# controller_main_board.net
KiCad netlist of a schematic drawn in EAGLE
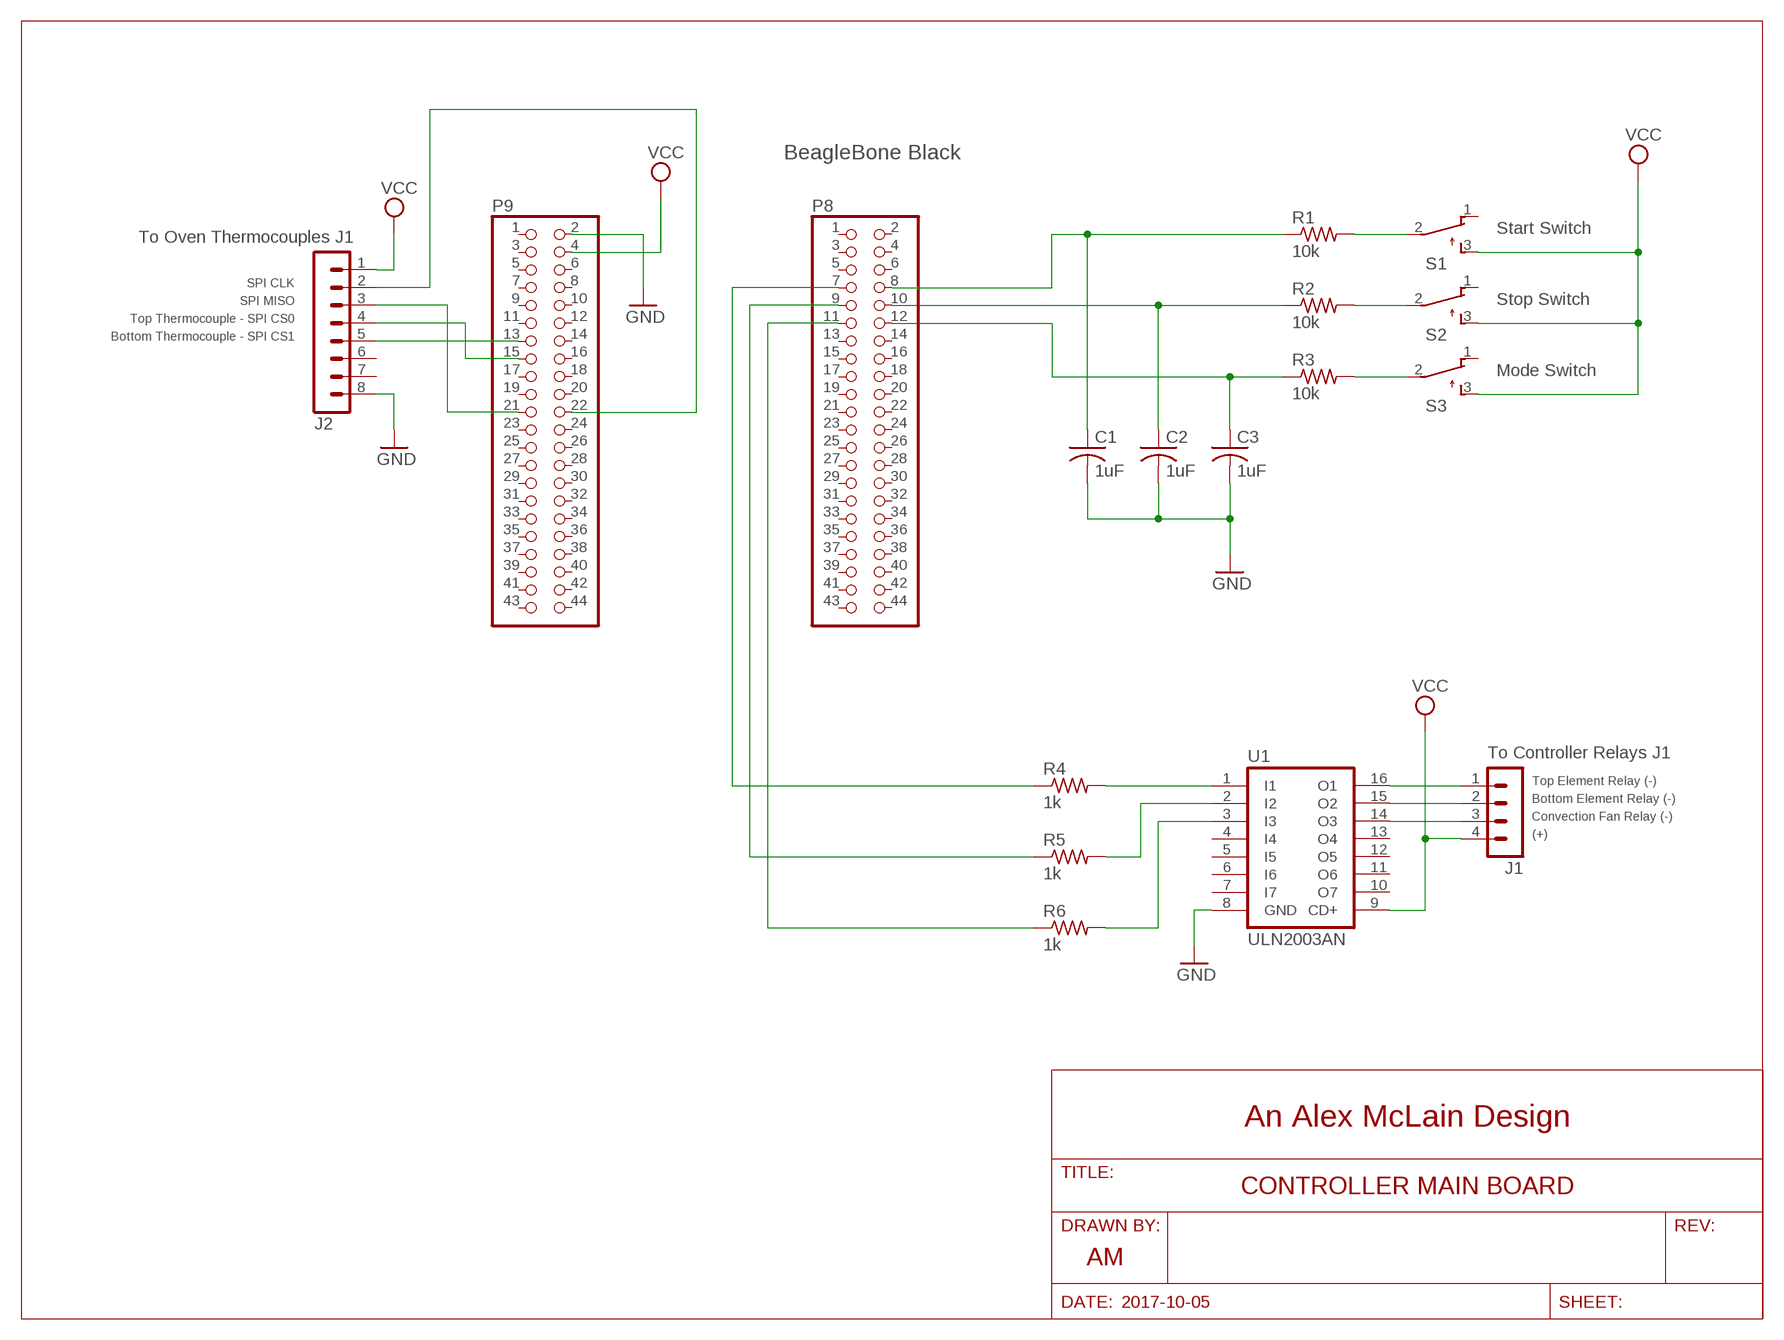
[diagram p0: schematic, sheet 1]

(export (version "E")
  (design (tool "Eeschema 10.0.6"))
  (components
    (comp (ref "C1")
      (value "1uF")
      (footprint "eagle-import:C025-050X050")
      (libsource (lib "eagle-import") (part "C-US025-050X050"))
    )
    (comp (ref "C2")
      (value "1uF")
      (footprint "eagle-import:C025-050X050")
      (libsource (lib "eagle-import") (part "C-US025-050X050"))
    )
    (comp (ref "C3")
      (value "1uF")
      (footprint "eagle-import:C025-050X050")
      (libsource (lib "eagle-import") (part "C-US025-050X050"))
    )
    (comp (ref "J1")
      (value "MA04-1")
      (footprint "eagle-import:MA04-1")
      (libsource (lib "eagle-import") (part "MA04-1"))
    )
    (comp (ref "J2")
      (value "MA08-1")
      (footprint "eagle-import:MA08-1")
      (libsource (lib "eagle-import") (part "MA08-1"))
    )
    (comp (ref "P8")
      (value "PINHD-2X22")
      (footprint "eagle-import:2X22")
      (libsource (lib "eagle-import") (part "PINHD-2X22"))
    )
    (comp (ref "P9")
      (value "PINHD-2X22")
      (footprint "eagle-import:2X22")
      (libsource (lib "eagle-import") (part "PINHD-2X22"))
    )
    (comp (ref "R1")
      (value "10k")
      (footprint "eagle-import:0204_7")
      (libsource (lib "eagle-import") (part "R-US_0204/7"))
    )
    (comp (ref "R2")
      (value "10k")
      (footprint "eagle-import:0204_7")
      (libsource (lib "eagle-import") (part "R-US_0204/7"))
    )
    (comp (ref "R3")
      (value "10k")
      (footprint "eagle-import:0204_7")
      (libsource (lib "eagle-import") (part "R-US_0204/7"))
    )
    (comp (ref "R4")
      (value "1k")
      (footprint "eagle-import:0204_7")
      (libsource (lib "eagle-import") (part "R-US_0204/7"))
    )
    (comp (ref "R5")
      (value "1k")
      (footprint "eagle-import:0204_7")
      (libsource (lib "eagle-import") (part "R-US_0204/7"))
    )
    (comp (ref "R6")
      (value "1k")
      (footprint "eagle-import:0204_7")
      (libsource (lib "eagle-import") (part "R-US_0204/7"))
    )
    (comp (ref "S1")
      (value "TL32PO")
      (footprint "eagle-import:TL3XPO")
      (libsource (lib "eagle-import") (part "TL32PO"))
    )
    (comp (ref "S2")
      (value "TL32PO")
      (footprint "eagle-import:TL3XPO")
      (libsource (lib "eagle-import") (part "TL32PO"))
    )
    (comp (ref "S3")
      (value "TL32PO")
      (footprint "eagle-import:TL3XPO")
      (libsource (lib "eagle-import") (part "TL32PO"))
    )
    (comp (ref "U1")
      (value "ULN2003AN")
      (footprint "eagle-import:DIL16")
      (libsource (lib "eagle-import") (part "ULN2003AN"))
    )
  )
  (nets
    (net (code "1") (name "GND") (class "Default")
      (node (ref "C1") (pin "2") (pinfunction "2_2") (pintype "passive"))
      (node (ref "C2") (pin "2") (pinfunction "2_2") (pintype "passive"))
      (node (ref "C3") (pin "2") (pinfunction "2_2") (pintype "passive"))
      (node (ref "J2") (pin "8") (pinfunction "8_8") (pintype "passive"))
      (node (ref "P9") (pin "2") (pinfunction "2_2") (pintype "passive"))
      (node (ref "U1") (pin "8") (pinfunction "GND_8") (pintype "power_in"))
    )
    (net (code "2") (name "Net-(C1-Pad1)") (class "Default")
      (node (ref "C1") (pin "1") (pinfunction "1_1") (pintype "passive"))
      (node (ref "P8") (pin "8") (pinfunction "8_8") (pintype "passive"))
      (node (ref "R1") (pin "1") (pinfunction "1_1") (pintype "passive"))
    )
    (net (code "3") (name "Net-(C2-Pad1)") (class "Default")
      (node (ref "C2") (pin "1") (pinfunction "1_1") (pintype "passive"))
      (node (ref "P8") (pin "10") (pinfunction "10_10") (pintype "passive"))
      (node (ref "R2") (pin "1") (pinfunction "1_1") (pintype "passive"))
    )
    (net (code "4") (name "Net-(C3-Pad1)") (class "Default")
      (node (ref "C3") (pin "1") (pinfunction "1_1") (pintype "passive"))
      (node (ref "P8") (pin "12") (pinfunction "12_12") (pintype "passive"))
      (node (ref "R3") (pin "1") (pinfunction "1_1") (pintype "passive"))
    )
    (net (code "5") (name "Net-(J2-Pad2)") (class "Default")
      (node (ref "J2") (pin "2") (pinfunction "2_2") (pintype "passive"))
      (node (ref "P9") (pin "22") (pinfunction "22_22") (pintype "passive"))
    )
    (net (code "6") (name "Net-(J2-Pad3)") (class "Default")
      (node (ref "J2") (pin "3") (pinfunction "3_3") (pintype "passive"))
      (node (ref "P9") (pin "21") (pinfunction "21_21") (pintype "passive"))
    )
    (net (code "7") (name "Net-(J2-Pad4)") (class "Default")
      (node (ref "J2") (pin "4") (pinfunction "4_4") (pintype "passive"))
      (node (ref "P9") (pin "15") (pinfunction "15_15") (pintype "passive"))
    )
    (net (code "8") (name "Net-(J2-Pad5)") (class "Default")
      (node (ref "J2") (pin "5") (pinfunction "5_5") (pintype "passive"))
      (node (ref "P9") (pin "13") (pinfunction "13_13") (pintype "passive"))
    )
    (net (code "9") (name "Net-(P8-Pad7)") (class "Default")
      (node (ref "P8") (pin "7") (pinfunction "7_7") (pintype "passive"))
      (node (ref "R4") (pin "1") (pinfunction "1_1") (pintype "passive"))
    )
    (net (code "10") (name "Net-(P8-Pad9)") (class "Default")
      (node (ref "P8") (pin "9") (pinfunction "9_9") (pintype "passive"))
      (node (ref "R5") (pin "1") (pinfunction "1_1") (pintype "passive"))
    )
    (net (code "11") (name "Net-(P8-Pad11)") (class "Default")
      (node (ref "P8") (pin "11") (pinfunction "11_11") (pintype "passive"))
      (node (ref "R6") (pin "1") (pinfunction "1_1") (pintype "passive"))
    )
    (net (code "12") (name "Net-(S1-P)") (class "Default")
      (node (ref "R1") (pin "2") (pinfunction "2_2") (pintype "passive"))
      (node (ref "S1") (pin "2") (pinfunction "P_2") (pintype "passive"))
    )
    (net (code "13") (name "Net-(S2-P)") (class "Default")
      (node (ref "R2") (pin "2") (pinfunction "2_2") (pintype "passive"))
      (node (ref "S2") (pin "2") (pinfunction "P_2") (pintype "passive"))
    )
    (net (code "14") (name "Net-(S3-P)") (class "Default")
      (node (ref "R3") (pin "2") (pinfunction "2_2") (pintype "passive"))
      (node (ref "S3") (pin "2") (pinfunction "P_2") (pintype "passive"))
    )
    (net (code "15") (name "Net-(U1-I1)") (class "Default")
      (node (ref "R4") (pin "2") (pinfunction "2_2") (pintype "passive"))
      (node (ref "U1") (pin "1") (pinfunction "I1_1") (pintype "input"))
    )
    (net (code "16") (name "Net-(U1-I2)") (class "Default")
      (node (ref "R5") (pin "2") (pinfunction "2_2") (pintype "passive"))
      (node (ref "U1") (pin "2") (pinfunction "I2_2") (pintype "input"))
    )
    (net (code "17") (name "Net-(U1-I3)") (class "Default")
      (node (ref "R6") (pin "2") (pinfunction "2_2") (pintype "passive"))
      (node (ref "U1") (pin "3") (pinfunction "I3_3") (pintype "input"))
    )
    (net (code "18") (name "Net-(U1-O1)") (class "Default")
      (node (ref "J1") (pin "1") (pinfunction "1_1") (pintype "passive"))
      (node (ref "U1") (pin "16") (pinfunction "O1_16") (pintype "open_collector"))
    )
    (net (code "19") (name "Net-(U1-O2)") (class "Default")
      (node (ref "J1") (pin "2") (pinfunction "2_2") (pintype "passive"))
      (node (ref "U1") (pin "15") (pinfunction "O2_15") (pintype "open_collector"))
    )
    (net (code "20") (name "Net-(U1-O3)") (class "Default")
      (node (ref "J1") (pin "3") (pinfunction "3_3") (pintype "passive"))
      (node (ref "U1") (pin "14") (pinfunction "O3_14") (pintype "open_collector"))
    )
    (net (code "21") (name "VCC") (class "Default")
      (node (ref "J1") (pin "4") (pinfunction "4_4") (pintype "passive"))
      (node (ref "J2") (pin "1") (pinfunction "1_1") (pintype "passive"))
      (node (ref "P9") (pin "4") (pinfunction "4_4") (pintype "passive"))
      (node (ref "S1") (pin "3") (pinfunction "S_3") (pintype "passive"))
      (node (ref "S2") (pin "3") (pinfunction "S_3") (pintype "passive"))
      (node (ref "S3") (pin "3") (pinfunction "S_3") (pintype "passive"))
      (node (ref "U1") (pin "9") (pinfunction "CD+_9") (pintype "passive"))
    )
    (net (code "22") (name "unconnected-(J2-Pad6)") (class "Default")
      (node (ref "J2") (pin "6") (pinfunction "6_6") (pintype "passive"))
    )
    (net (code "23") (name "unconnected-(J2-Pad7)") (class "Default")
      (node (ref "J2") (pin "7") (pinfunction "7_7") (pintype "passive"))
    )
    (net (code "24") (name "unconnected-(P8-Pad1)") (class "Default")
      (node (ref "P8") (pin "1") (pinfunction "1_1") (pintype "passive"))
    )
    (net (code "25") (name "unconnected-(P8-Pad2)") (class "Default")
      (node (ref "P8") (pin "2") (pinfunction "2_2") (pintype "passive"))
    )
    (net (code "26") (name "unconnected-(P8-Pad3)") (class "Default")
      (node (ref "P8") (pin "3") (pinfunction "3_3") (pintype "passive"))
    )
    (net (code "27") (name "unconnected-(P8-Pad4)") (class "Default")
      (node (ref "P8") (pin "4") (pinfunction "4_4") (pintype "passive"))
    )
    (net (code "28") (name "unconnected-(P8-Pad5)") (class "Default")
      (node (ref "P8") (pin "5") (pinfunction "5_5") (pintype "passive"))
    )
    (net (code "29") (name "unconnected-(P8-Pad6)") (class "Default")
      (node (ref "P8") (pin "6") (pinfunction "6_6") (pintype "passive"))
    )
    (net (code "30") (name "unconnected-(P8-Pad13)") (class "Default")
      (node (ref "P8") (pin "13") (pinfunction "13_13") (pintype "passive"))
    )
    (net (code "31") (name "unconnected-(P8-Pad14)") (class "Default")
      (node (ref "P8") (pin "14") (pinfunction "14_14") (pintype "passive"))
    )
    (net (code "32") (name "unconnected-(P8-Pad15)") (class "Default")
      (node (ref "P8") (pin "15") (pinfunction "15_15") (pintype "passive"))
    )
    (net (code "33") (name "unconnected-(P8-Pad16)") (class "Default")
      (node (ref "P8") (pin "16") (pinfunction "16_16") (pintype "passive"))
    )
    (net (code "34") (name "unconnected-(P8-Pad17)") (class "Default")
      (node (ref "P8") (pin "17") (pinfunction "17_17") (pintype "passive"))
    )
    (net (code "35") (name "unconnected-(P8-Pad18)") (class "Default")
      (node (ref "P8") (pin "18") (pinfunction "18_18") (pintype "passive"))
    )
    (net (code "36") (name "unconnected-(P8-Pad19)") (class "Default")
      (node (ref "P8") (pin "19") (pinfunction "19_19") (pintype "passive"))
    )
    (net (code "37") (name "unconnected-(P8-Pad20)") (class "Default")
      (node (ref "P8") (pin "20") (pinfunction "20_20") (pintype "passive"))
    )
    (net (code "38") (name "unconnected-(P8-Pad21)") (class "Default")
      (node (ref "P8") (pin "21") (pinfunction "21_21") (pintype "passive"))
    )
    (net (code "39") (name "unconnected-(P8-Pad22)") (class "Default")
      (node (ref "P8") (pin "22") (pinfunction "22_22") (pintype "passive"))
    )
    (net (code "40") (name "unconnected-(P8-Pad23)") (class "Default")
      (node (ref "P8") (pin "23") (pinfunction "23_23") (pintype "passive"))
    )
    (net (code "41") (name "unconnected-(P8-Pad24)") (class "Default")
      (node (ref "P8") (pin "24") (pinfunction "24_24") (pintype "passive"))
    )
    (net (code "42") (name "unconnected-(P8-Pad25)") (class "Default")
      (node (ref "P8") (pin "25") (pinfunction "25_25") (pintype "passive"))
    )
    (net (code "43") (name "unconnected-(P8-Pad26)") (class "Default")
      (node (ref "P8") (pin "26") (pinfunction "26_26") (pintype "passive"))
    )
    (net (code "44") (name "unconnected-(P8-Pad27)") (class "Default")
      (node (ref "P8") (pin "27") (pinfunction "27_27") (pintype "passive"))
    )
    (net (code "45") (name "unconnected-(P8-Pad28)") (class "Default")
      (node (ref "P8") (pin "28") (pinfunction "28_28") (pintype "passive"))
    )
    (net (code "46") (name "unconnected-(P8-Pad29)") (class "Default")
      (node (ref "P8") (pin "29") (pinfunction "29_29") (pintype "passive"))
    )
    (net (code "47") (name "unconnected-(P8-Pad30)") (class "Default")
      (node (ref "P8") (pin "30") (pinfunction "30_30") (pintype "passive"))
    )
    (net (code "48") (name "unconnected-(P8-Pad31)") (class "Default")
      (node (ref "P8") (pin "31") (pinfunction "31_31") (pintype "passive"))
    )
    (net (code "49") (name "unconnected-(P8-Pad32)") (class "Default")
      (node (ref "P8") (pin "32") (pinfunction "32_32") (pintype "passive"))
    )
    (net (code "50") (name "unconnected-(P8-Pad33)") (class "Default")
      (node (ref "P8") (pin "33") (pinfunction "33_33") (pintype "passive"))
    )
    (net (code "51") (name "unconnected-(P8-Pad34)") (class "Default")
      (node (ref "P8") (pin "34") (pinfunction "34_34") (pintype "passive"))
    )
    (net (code "52") (name "unconnected-(P8-Pad35)") (class "Default")
      (node (ref "P8") (pin "35") (pinfunction "35_35") (pintype "passive"))
    )
    (net (code "53") (name "unconnected-(P8-Pad36)") (class "Default")
      (node (ref "P8") (pin "36") (pinfunction "36_36") (pintype "passive"))
    )
    (net (code "54") (name "unconnected-(P8-Pad37)") (class "Default")
      (node (ref "P8") (pin "37") (pinfunction "37_37") (pintype "passive"))
    )
    (net (code "55") (name "unconnected-(P8-Pad38)") (class "Default")
      (node (ref "P8") (pin "38") (pinfunction "38_38") (pintype "passive"))
    )
    (net (code "56") (name "unconnected-(P8-Pad39)") (class "Default")
      (node (ref "P8") (pin "39") (pinfunction "39_39") (pintype "passive"))
    )
    (net (code "57") (name "unconnected-(P8-Pad40)") (class "Default")
      (node (ref "P8") (pin "40") (pinfunction "40_40") (pintype "passive"))
    )
    (net (code "58") (name "unconnected-(P8-Pad41)") (class "Default")
      (node (ref "P8") (pin "41") (pinfunction "41_41") (pintype "passive"))
    )
    (net (code "59") (name "unconnected-(P8-Pad42)") (class "Default")
      (node (ref "P8") (pin "42") (pinfunction "42_42") (pintype "passive"))
    )
    (net (code "60") (name "unconnected-(P8-Pad43)") (class "Default")
      (node (ref "P8") (pin "43") (pinfunction "43_43") (pintype "passive"))
    )
    (net (code "61") (name "unconnected-(P8-Pad44)") (class "Default")
      (node (ref "P8") (pin "44") (pinfunction "44_44") (pintype "passive"))
    )
    (net (code "62") (name "unconnected-(P9-Pad1)") (class "Default")
      (node (ref "P9") (pin "1") (pinfunction "1_1") (pintype "passive"))
    )
    (net (code "63") (name "unconnected-(P9-Pad3)") (class "Default")
      (node (ref "P9") (pin "3") (pinfunction "3_3") (pintype "passive"))
    )
    (net (code "64") (name "unconnected-(P9-Pad5)") (class "Default")
      (node (ref "P9") (pin "5") (pinfunction "5_5") (pintype "passive"))
    )
    (net (code "65") (name "unconnected-(P9-Pad6)") (class "Default")
      (node (ref "P9") (pin "6") (pinfunction "6_6") (pintype "passive"))
    )
    (net (code "66") (name "unconnected-(P9-Pad7)") (class "Default")
      (node (ref "P9") (pin "7") (pinfunction "7_7") (pintype "passive"))
    )
    (net (code "67") (name "unconnected-(P9-Pad8)") (class "Default")
      (node (ref "P9") (pin "8") (pinfunction "8_8") (pintype "passive"))
    )
    (net (code "68") (name "unconnected-(P9-Pad9)") (class "Default")
      (node (ref "P9") (pin "9") (pinfunction "9_9") (pintype "passive"))
    )
    (net (code "69") (name "unconnected-(P9-Pad10)") (class "Default")
      (node (ref "P9") (pin "10") (pinfunction "10_10") (pintype "passive"))
    )
    (net (code "70") (name "unconnected-(P9-Pad11)") (class "Default")
      (node (ref "P9") (pin "11") (pinfunction "11_11") (pintype "passive"))
    )
    (net (code "71") (name "unconnected-(P9-Pad12)") (class "Default")
      (node (ref "P9") (pin "12") (pinfunction "12_12") (pintype "passive"))
    )
    (net (code "72") (name "unconnected-(P9-Pad14)") (class "Default")
      (node (ref "P9") (pin "14") (pinfunction "14_14") (pintype "passive"))
    )
    (net (code "73") (name "unconnected-(P9-Pad16)") (class "Default")
      (node (ref "P9") (pin "16") (pinfunction "16_16") (pintype "passive"))
    )
    (net (code "74") (name "unconnected-(P9-Pad17)") (class "Default")
      (node (ref "P9") (pin "17") (pinfunction "17_17") (pintype "passive"))
    )
    (net (code "75") (name "unconnected-(P9-Pad18)") (class "Default")
      (node (ref "P9") (pin "18") (pinfunction "18_18") (pintype "passive"))
    )
    (net (code "76") (name "unconnected-(P9-Pad19)") (class "Default")
      (node (ref "P9") (pin "19") (pinfunction "19_19") (pintype "passive"))
    )
    (net (code "77") (name "unconnected-(P9-Pad20)") (class "Default")
      (node (ref "P9") (pin "20") (pinfunction "20_20") (pintype "passive"))
    )
    (net (code "78") (name "unconnected-(P9-Pad23)") (class "Default")
      (node (ref "P9") (pin "23") (pinfunction "23_23") (pintype "passive"))
    )
    (net (code "79") (name "unconnected-(P9-Pad24)") (class "Default")
      (node (ref "P9") (pin "24") (pinfunction "24_24") (pintype "passive"))
    )
    (net (code "80") (name "unconnected-(P9-Pad25)") (class "Default")
      (node (ref "P9") (pin "25") (pinfunction "25_25") (pintype "passive"))
    )
    (net (code "81") (name "unconnected-(P9-Pad26)") (class "Default")
      (node (ref "P9") (pin "26") (pinfunction "26_26") (pintype "passive"))
    )
    (net (code "82") (name "unconnected-(P9-Pad27)") (class "Default")
      (node (ref "P9") (pin "27") (pinfunction "27_27") (pintype "passive"))
    )
    (net (code "83") (name "unconnected-(P9-Pad28)") (class "Default")
      (node (ref "P9") (pin "28") (pinfunction "28_28") (pintype "passive"))
    )
    (net (code "84") (name "unconnected-(P9-Pad29)") (class "Default")
      (node (ref "P9") (pin "29") (pinfunction "29_29") (pintype "passive"))
    )
    (net (code "85") (name "unconnected-(P9-Pad30)") (class "Default")
      (node (ref "P9") (pin "30") (pinfunction "30_30") (pintype "passive"))
    )
    (net (code "86") (name "unconnected-(P9-Pad31)") (class "Default")
      (node (ref "P9") (pin "31") (pinfunction "31_31") (pintype "passive"))
    )
    (net (code "87") (name "unconnected-(P9-Pad32)") (class "Default")
      (node (ref "P9") (pin "32") (pinfunction "32_32") (pintype "passive"))
    )
    (net (code "88") (name "unconnected-(P9-Pad33)") (class "Default")
      (node (ref "P9") (pin "33") (pinfunction "33_33") (pintype "passive"))
    )
    (net (code "89") (name "unconnected-(P9-Pad34)") (class "Default")
      (node (ref "P9") (pin "34") (pinfunction "34_34") (pintype "passive"))
    )
    (net (code "90") (name "unconnected-(P9-Pad35)") (class "Default")
      (node (ref "P9") (pin "35") (pinfunction "35_35") (pintype "passive"))
    )
    (net (code "91") (name "unconnected-(P9-Pad36)") (class "Default")
      (node (ref "P9") (pin "36") (pinfunction "36_36") (pintype "passive"))
    )
    (net (code "92") (name "unconnected-(P9-Pad37)") (class "Default")
      (node (ref "P9") (pin "37") (pinfunction "37_37") (pintype "passive"))
    )
    (net (code "93") (name "unconnected-(P9-Pad38)") (class "Default")
      (node (ref "P9") (pin "38") (pinfunction "38_38") (pintype "passive"))
    )
    (net (code "94") (name "unconnected-(P9-Pad39)") (class "Default")
      (node (ref "P9") (pin "39") (pinfunction "39_39") (pintype "passive"))
    )
    (net (code "95") (name "unconnected-(P9-Pad40)") (class "Default")
      (node (ref "P9") (pin "40") (pinfunction "40_40") (pintype "passive"))
    )
    (net (code "96") (name "unconnected-(P9-Pad41)") (class "Default")
      (node (ref "P9") (pin "41") (pinfunction "41_41") (pintype "passive"))
    )
    (net (code "97") (name "unconnected-(P9-Pad42)") (class "Default")
      (node (ref "P9") (pin "42") (pinfunction "42_42") (pintype "passive"))
    )
    (net (code "98") (name "unconnected-(P9-Pad43)") (class "Default")
      (node (ref "P9") (pin "43") (pinfunction "43_43") (pintype "passive"))
    )
    (net (code "99") (name "unconnected-(P9-Pad44)") (class "Default")
      (node (ref "P9") (pin "44") (pinfunction "44_44") (pintype "passive"))
    )
    (net (code "100") (name "unconnected-(S1-O-Pad1)") (class "Default")
      (node (ref "S1") (pin "1") (pinfunction "O_1") (pintype "passive"))
    )
    (net (code "101") (name "unconnected-(S2-O-Pad1)") (class "Default")
      (node (ref "S2") (pin "1") (pinfunction "O_1") (pintype "passive"))
    )
    (net (code "102") (name "unconnected-(S3-O-Pad1)") (class "Default")
      (node (ref "S3") (pin "1") (pinfunction "O_1") (pintype "passive"))
    )
    (net (code "103") (name "unconnected-(U1-I4-Pad4)") (class "Default")
      (node (ref "U1") (pin "4") (pinfunction "I4_4") (pintype "input"))
    )
    (net (code "104") (name "unconnected-(U1-I5-Pad5)") (class "Default")
      (node (ref "U1") (pin "5") (pinfunction "I5_5") (pintype "input"))
    )
    (net (code "105") (name "unconnected-(U1-I6-Pad6)") (class "Default")
      (node (ref "U1") (pin "6") (pinfunction "I6_6") (pintype "input"))
    )
    (net (code "106") (name "unconnected-(U1-I7-Pad7)") (class "Default")
      (node (ref "U1") (pin "7") (pinfunction "I7_7") (pintype "input"))
    )
    (net (code "107") (name "unconnected-(U1-O4-Pad13)") (class "Default")
      (node (ref "U1") (pin "13") (pinfunction "O4_13") (pintype "open_collector"))
    )
    (net (code "108") (name "unconnected-(U1-O5-Pad12)") (class "Default")
      (node (ref "U1") (pin "12") (pinfunction "O5_12") (pintype "open_collector"))
    )
    (net (code "109") (name "unconnected-(U1-O6-Pad11)") (class "Default")
      (node (ref "U1") (pin "11") (pinfunction "O6_11") (pintype "open_collector"))
    )
    (net (code "110") (name "unconnected-(U1-O7-Pad10)") (class "Default")
      (node (ref "U1") (pin "10") (pinfunction "O7_10") (pintype "open_collector"))
    )
  )
)
